# rapidshark-lipo-sensor-mk-3_5.net
KiCad netlist of a schematic drawn in EAGLE
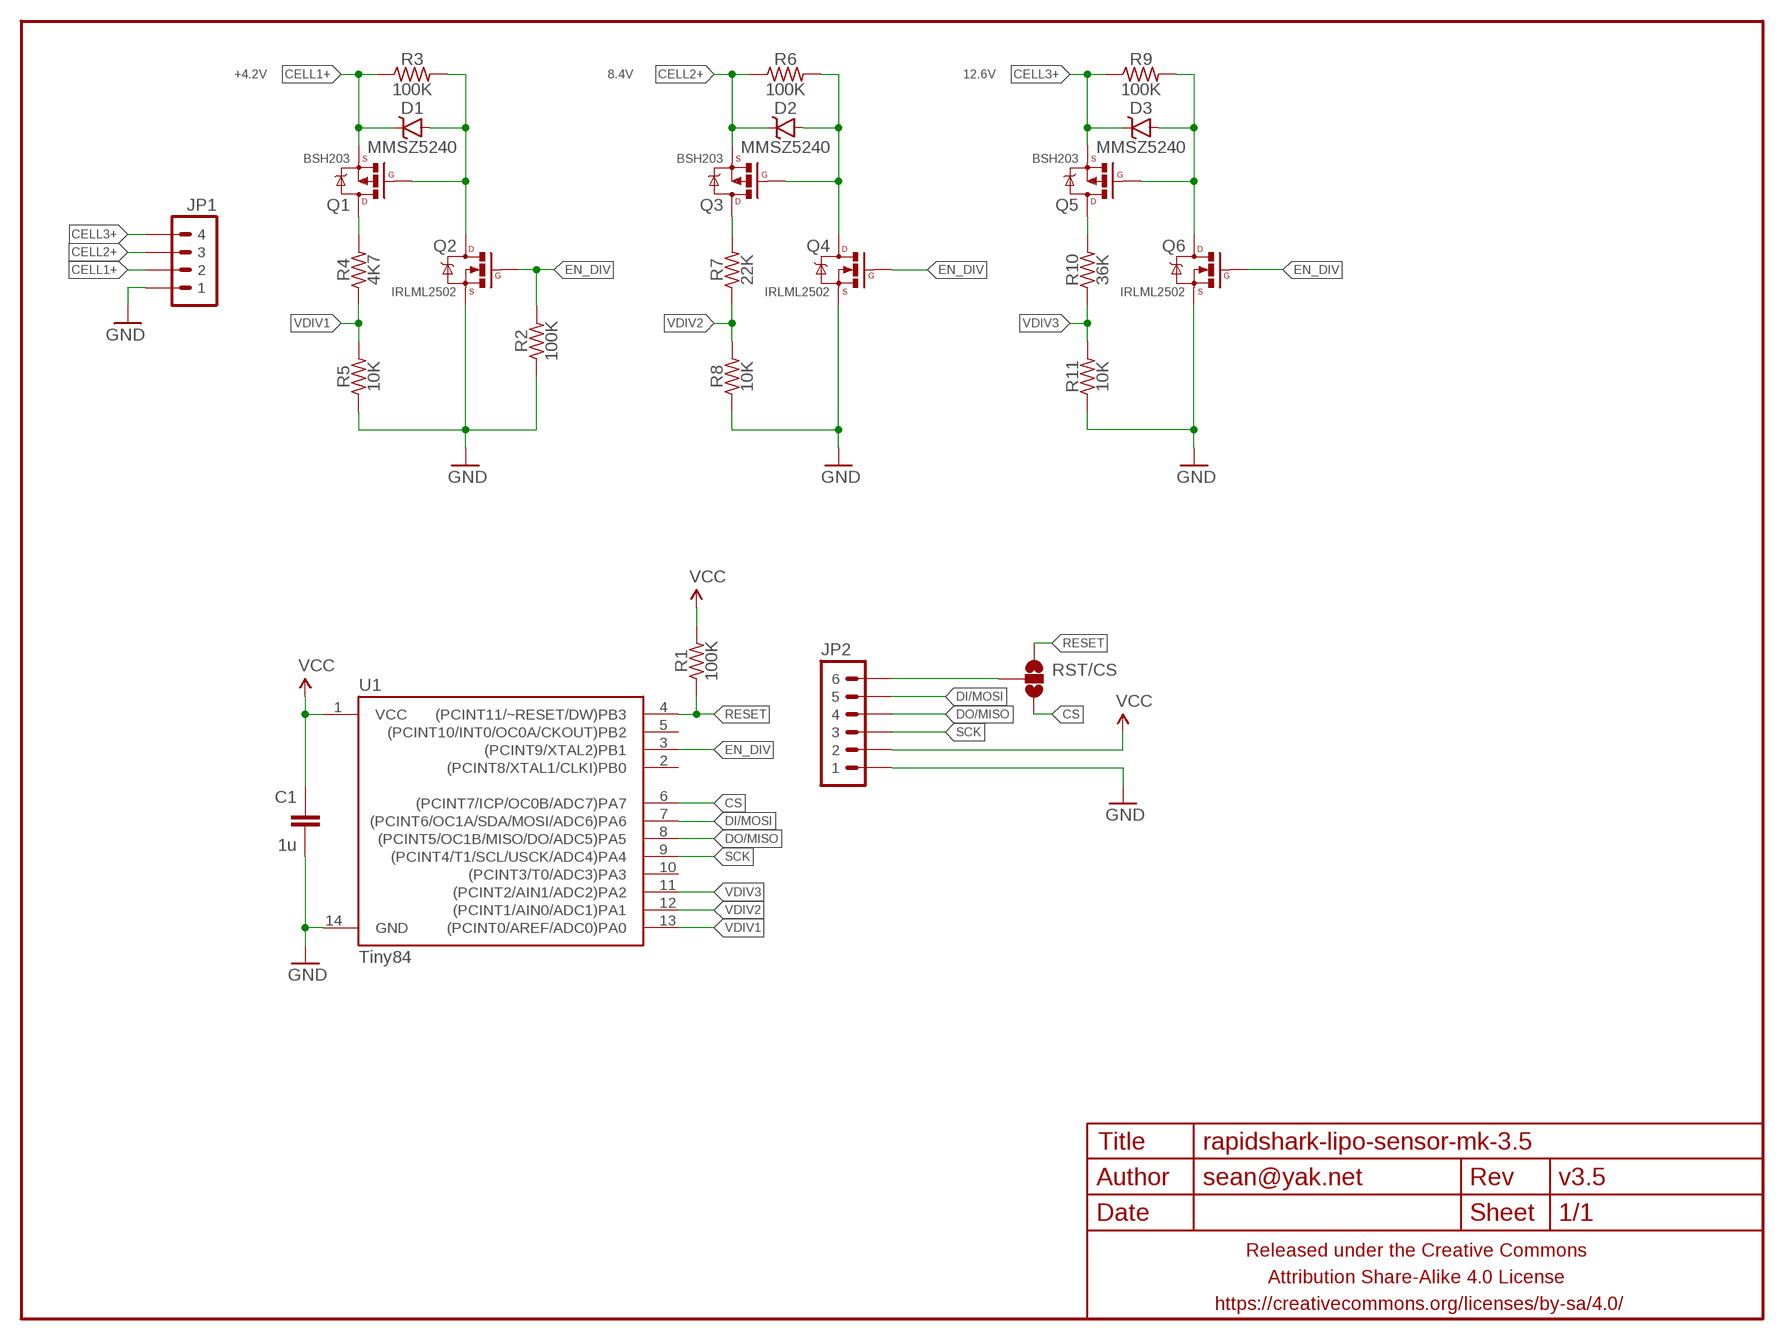
[diagram p0: schematic, sheet 1]

(export (version "E")
  (design (tool "Eeschema 10.0.6"))
  (components
    (comp (ref "C1")
      (value "1u")
      (footprint "eagle-import:C0603-TIGHTER")
      (libsource (lib "eagle-import") (part "CAPACITOR-CERAMICC0603-TIGHTER"))
    )
    (comp (ref "D1")
      (value "MMSZ5240")
      (footprint "eagle-import:SOD323-ZENNER")
      (libsource (lib "eagle-import") (part "DIODE-ZENERSOD323"))
    )
    (comp (ref "D2")
      (value "MMSZ5240")
      (footprint "eagle-import:SOD323-ZENNER")
      (libsource (lib "eagle-import") (part "DIODE-ZENERSOD323"))
    )
    (comp (ref "D3")
      (value "MMSZ5240")
      (footprint "eagle-import:SOD323-ZENNER")
      (libsource (lib "eagle-import") (part "DIODE-ZENERSOD323"))
    )
    (comp (ref "FRAME1")
      (value "FRAME-LETTERNO_PACKAGE")
      (footprint "eagle-import:DUMMY")
      (fields (field (name "DESIGNER") "sean@yak.net") (field (name "VERSION") "v3.5"))
      (libsource (lib "eagle-import") (part "FRAME-LETTERNO_PACKAGE"))
    )
    (comp (ref "JP1")
      (value "M04JST_XH_RA")
      (footprint "eagle-import:JST-4-XH-RA-PTH")
      (libsource (lib "eagle-import") (part "M04JST_XH_RA"))
    )
    (comp (ref "JP2")
      (value "M06PTH_CENTERED")
      (footprint "eagle-import:1X06_CENTERED")
      (libsource (lib "eagle-import") (part "M06PTH_CENTERED"))
    )
    (comp (ref "Q1")
      (value "BSH203")
      (footprint "eagle-import:SOT23")
      (libsource (lib "eagle-import") (part "MOSFET-PCHANNELSOT-23"))
    )
    (comp (ref "Q2")
      (value "IRLML2502")
      (footprint "eagle-import:SOT23")
      (libsource (lib "eagle-import") (part "MOSFET-NCHANNELIRLML2502"))
    )
    (comp (ref "Q3")
      (value "BSH203")
      (footprint "eagle-import:SOT23")
      (libsource (lib "eagle-import") (part "MOSFET-PCHANNELSOT-23"))
    )
    (comp (ref "Q4")
      (value "IRLML2502")
      (footprint "eagle-import:SOT23")
      (libsource (lib "eagle-import") (part "MOSFET-NCHANNELIRLML2502"))
    )
    (comp (ref "Q5")
      (value "BSH203")
      (footprint "eagle-import:SOT23")
      (libsource (lib "eagle-import") (part "MOSFET-PCHANNELSOT-23"))
    )
    (comp (ref "Q6")
      (value "IRLML2502")
      (footprint "eagle-import:SOT23")
      (libsource (lib "eagle-import") (part "MOSFET-NCHANNELIRLML2502"))
    )
    (comp (ref "R1")
      (value "100K")
      (footprint "eagle-import:R0603-TIGHTER")
      (libsource (lib "eagle-import") (part "RESISTORR0603-TIGHTER"))
    )
    (comp (ref "R2")
      (value "100K")
      (footprint "eagle-import:R0603-TIGHTER")
      (libsource (lib "eagle-import") (part "RESISTORR0603-TIGHTER"))
    )
    (comp (ref "R3")
      (value "100K")
      (footprint "eagle-import:R0603-TIGHTER")
      (libsource (lib "eagle-import") (part "RESISTORR0603-TIGHTER"))
    )
    (comp (ref "R4")
      (value "4K7")
      (footprint "eagle-import:R0603-TIGHTER")
      (libsource (lib "eagle-import") (part "RESISTORR0603-TIGHTER"))
    )
    (comp (ref "R5")
      (value "10K")
      (footprint "eagle-import:R0603-TIGHTER")
      (libsource (lib "eagle-import") (part "RESISTORR0603-TIGHTER"))
    )
    (comp (ref "R6")
      (value "100K")
      (footprint "eagle-import:R0603-TIGHTER")
      (libsource (lib "eagle-import") (part "RESISTORR0603-TIGHTER"))
    )
    (comp (ref "R7")
      (value "22K")
      (footprint "eagle-import:R0603-TIGHTER")
      (libsource (lib "eagle-import") (part "RESISTORR0603-TIGHTER"))
    )
    (comp (ref "R8")
      (value "10K")
      (footprint "eagle-import:R0603-TIGHTER")
      (libsource (lib "eagle-import") (part "RESISTORR0603-TIGHTER"))
    )
    (comp (ref "R9")
      (value "100K")
      (footprint "eagle-import:R0603-TIGHTER")
      (libsource (lib "eagle-import") (part "RESISTORR0603-TIGHTER"))
    )
    (comp (ref "R10")
      (value "36K")
      (footprint "eagle-import:R0603-TIGHTER")
      (libsource (lib "eagle-import") (part "RESISTORR0603-TIGHTER"))
    )
    (comp (ref "R11")
      (value "10K")
      (footprint "eagle-import:R0603-TIGHTER")
      (libsource (lib "eagle-import") (part "RESISTORR0603-TIGHTER"))
    )
    (comp (ref "RST/CS")
      (value "JUMPER-PAD-3-NOFULL_BOX_SILK")
      (footprint "eagle-import:PAD-JUMPER-3-NO_YES_SILK_FULL_BOX")
      (libsource (lib "eagle-import") (part "JUMPER-PAD-3-NOFULL_BOX_SILK"))
    )
    (comp (ref "U1")
      (value "Tiny84")
      (footprint "eagle-import:SO14")
      (libsource (lib "eagle-import") (part "ATTINY84"))
    )
  )
  (nets
    (net (code "1") (name "CELL1+") (class "Default")
      (node (ref "D1") (pin "C") (pinfunction "C_C") (pintype "passive"))
      (node (ref "JP1") (pin "2") (pinfunction "2_2") (pintype "passive"))
      (node (ref "Q1") (pin "2") (pinfunction "S_2") (pintype "passive"))
      (node (ref "R3") (pin "1") (pinfunction "1_1") (pintype "passive"))
    )
    (net (code "2") (name "CELL2+") (class "Default")
      (node (ref "D2") (pin "C") (pinfunction "C_C") (pintype "passive"))
      (node (ref "JP1") (pin "3") (pinfunction "3_3") (pintype "passive"))
      (node (ref "Q3") (pin "2") (pinfunction "S_2") (pintype "passive"))
      (node (ref "R6") (pin "1") (pinfunction "1_1") (pintype "passive"))
    )
    (net (code "3") (name "CELL3+") (class "Default")
      (node (ref "D3") (pin "C") (pinfunction "C_C") (pintype "passive"))
      (node (ref "JP1") (pin "4") (pinfunction "4_4") (pintype "passive"))
      (node (ref "Q5") (pin "2") (pinfunction "S_2") (pintype "passive"))
      (node (ref "R9") (pin "1") (pinfunction "1_1") (pintype "passive"))
    )
    (net (code "4") (name "CS") (class "Default")
      (node (ref "RST/CS") (pin "3") (pinfunction "3_3") (pintype "passive"))
      (node (ref "U1") (pin "6") (pinfunction "(PCINT7/ICP/OC0B/ADC7)PA7_6") (pintype "bidirectional"))
    )
    (net (code "5") (name "DI{slash}MOSI") (class "Default")
      (node (ref "JP2") (pin "5") (pinfunction "5_5") (pintype "passive"))
      (node (ref "U1") (pin "7") (pinfunction "(PCINT6/OC1A/SDA/MOSI/ADC6)PA6_7") (pintype "bidirectional"))
    )
    (net (code "6") (name "DO{slash}MISO") (class "Default")
      (node (ref "JP2") (pin "4") (pinfunction "4_4") (pintype "passive"))
      (node (ref "U1") (pin "8") (pinfunction "(PCINT5/OC1B/MISO/DO/ADC5)PA5_8") (pintype "bidirectional"))
    )
    (net (code "7") (name "EN_DIV") (class "Default")
      (node (ref "Q2") (pin "1") (pinfunction "G_1") (pintype "passive"))
      (node (ref "Q4") (pin "1") (pinfunction "G_1") (pintype "passive"))
      (node (ref "Q6") (pin "1") (pinfunction "G_1") (pintype "passive"))
      (node (ref "R2") (pin "2") (pinfunction "2_2") (pintype "passive"))
      (node (ref "U1") (pin "3") (pinfunction "(PCINT9/XTAL2)PB1_3") (pintype "bidirectional"))
    )
    (net (code "8") (name "GND") (class "Default")
      (node (ref "C1") (pin "2") (pinfunction "2_2") (pintype "passive"))
      (node (ref "JP1") (pin "1") (pinfunction "1_1") (pintype "passive"))
      (node (ref "JP2") (pin "1") (pinfunction "1_1") (pintype "passive"))
      (node (ref "Q2") (pin "2") (pinfunction "S_2") (pintype "passive"))
      (node (ref "Q4") (pin "2") (pinfunction "S_2") (pintype "passive"))
      (node (ref "Q6") (pin "2") (pinfunction "S_2") (pintype "passive"))
      (node (ref "R11") (pin "1") (pinfunction "1_1") (pintype "passive"))
      (node (ref "R2") (pin "1") (pinfunction "1_1") (pintype "passive"))
      (node (ref "R5") (pin "1") (pinfunction "1_1") (pintype "passive"))
      (node (ref "R8") (pin "1") (pinfunction "1_1") (pintype "passive"))
      (node (ref "U1") (pin "14") (pinfunction "GND_14") (pintype "bidirectional"))
    )
    (net (code "9") (name "Net-(JP2-Pad6)") (class "Default")
      (node (ref "JP2") (pin "6") (pinfunction "6_6") (pintype "passive"))
      (node (ref "RST/CS") (pin "2") (pinfunction "2_2") (pintype "passive"))
    )
    (net (code "10") (name "Net-(Q1-D)") (class "Default")
      (node (ref "Q1") (pin "3") (pinfunction "D_3") (pintype "passive"))
      (node (ref "R4") (pin "2") (pinfunction "2_2") (pintype "passive"))
    )
    (net (code "11") (name "Net-(Q1-G)") (class "Default")
      (node (ref "D1") (pin "A") (pinfunction "A_A") (pintype "passive"))
      (node (ref "Q1") (pin "1") (pinfunction "G_1") (pintype "passive"))
      (node (ref "Q2") (pin "3") (pinfunction "D_3") (pintype "passive"))
      (node (ref "R3") (pin "2") (pinfunction "2_2") (pintype "passive"))
    )
    (net (code "12") (name "Net-(Q3-D)") (class "Default")
      (node (ref "Q3") (pin "3") (pinfunction "D_3") (pintype "passive"))
      (node (ref "R7") (pin "2") (pinfunction "2_2") (pintype "passive"))
    )
    (net (code "13") (name "Net-(Q3-G)") (class "Default")
      (node (ref "D2") (pin "A") (pinfunction "A_A") (pintype "passive"))
      (node (ref "Q3") (pin "1") (pinfunction "G_1") (pintype "passive"))
      (node (ref "Q4") (pin "3") (pinfunction "D_3") (pintype "passive"))
      (node (ref "R6") (pin "2") (pinfunction "2_2") (pintype "passive"))
    )
    (net (code "14") (name "Net-(Q5-D)") (class "Default")
      (node (ref "Q5") (pin "3") (pinfunction "D_3") (pintype "passive"))
      (node (ref "R10") (pin "2") (pinfunction "2_2") (pintype "passive"))
    )
    (net (code "15") (name "Net-(Q5-G)") (class "Default")
      (node (ref "D3") (pin "A") (pinfunction "A_A") (pintype "passive"))
      (node (ref "Q5") (pin "1") (pinfunction "G_1") (pintype "passive"))
      (node (ref "Q6") (pin "3") (pinfunction "D_3") (pintype "passive"))
      (node (ref "R9") (pin "2") (pinfunction "2_2") (pintype "passive"))
    )
    (net (code "16") (name "RESET") (class "Default")
      (node (ref "R1") (pin "1") (pinfunction "1_1") (pintype "passive"))
      (node (ref "RST/CS") (pin "1") (pinfunction "1_1") (pintype "passive"))
      (node (ref "U1") (pin "4") (pinfunction "(PCINT11/~{RESET/DW})PB3_4") (pintype "bidirectional"))
    )
    (net (code "17") (name "SCK") (class "Default")
      (node (ref "JP2") (pin "3") (pinfunction "3_3") (pintype "passive"))
      (node (ref "U1") (pin "9") (pinfunction "(PCINT4/T1/SCL/USCK/ADC4)PA4_9") (pintype "bidirectional"))
    )
    (net (code "18") (name "VCC") (class "Default")
      (node (ref "C1") (pin "1") (pinfunction "1_1") (pintype "passive"))
      (node (ref "JP2") (pin "2") (pinfunction "2_2") (pintype "passive"))
      (node (ref "R1") (pin "2") (pinfunction "2_2") (pintype "passive"))
      (node (ref "U1") (pin "1") (pinfunction "VCC_1") (pintype "bidirectional"))
    )
    (net (code "19") (name "VDIV1") (class "Default")
      (node (ref "R4") (pin "1") (pinfunction "1_1") (pintype "passive"))
      (node (ref "R5") (pin "2") (pinfunction "2_2") (pintype "passive"))
      (node (ref "U1") (pin "13") (pinfunction "(PCINT0/AREF/ADC0)PA0_13") (pintype "bidirectional"))
    )
    (net (code "20") (name "VDIV2") (class "Default")
      (node (ref "R7") (pin "1") (pinfunction "1_1") (pintype "passive"))
      (node (ref "R8") (pin "2") (pinfunction "2_2") (pintype "passive"))
      (node (ref "U1") (pin "12") (pinfunction "(PCINT1/AIN0/ADC1)PA1_12") (pintype "bidirectional"))
    )
    (net (code "21") (name "VDIV3") (class "Default")
      (node (ref "R10") (pin "1") (pinfunction "1_1") (pintype "passive"))
      (node (ref "R11") (pin "2") (pinfunction "2_2") (pintype "passive"))
      (node (ref "U1") (pin "11") (pinfunction "(PCINT2/AIN1/ADC2)PA2_11") (pintype "bidirectional"))
    )
    (net (code "22") (name "unconnected-(U1-(PCINT3{slash}T0{slash}ADC3)PA3-Pad10)") (class "Default")
      (node (ref "U1") (pin "10") (pinfunction "(PCINT3/T0/ADC3)PA3_10") (pintype "bidirectional"))
    )
    (net (code "23") (name "unconnected-(U1-(PCINT8{slash}XTAL1{slash}CLKI)PB0-Pad2)") (class "Default")
      (node (ref "U1") (pin "2") (pinfunction "(PCINT8/XTAL1/CLKI)PB0_2") (pintype "bidirectional"))
    )
    (net (code "24") (name "unconnected-(U1-(PCINT10{slash}INT0{slash}OC0A{slash}CKOUT)PB2-Pad5)") (class "Default")
      (node (ref "U1") (pin "5") (pinfunction "(PCINT10/INT0/OC0A/CKOUT)PB2_5") (pintype "bidirectional"))
    )
  )
)
